# HIVE_SIGHT_DECAWAVE_A.net
KiCad netlist of a schematic drawn in Altium Designer
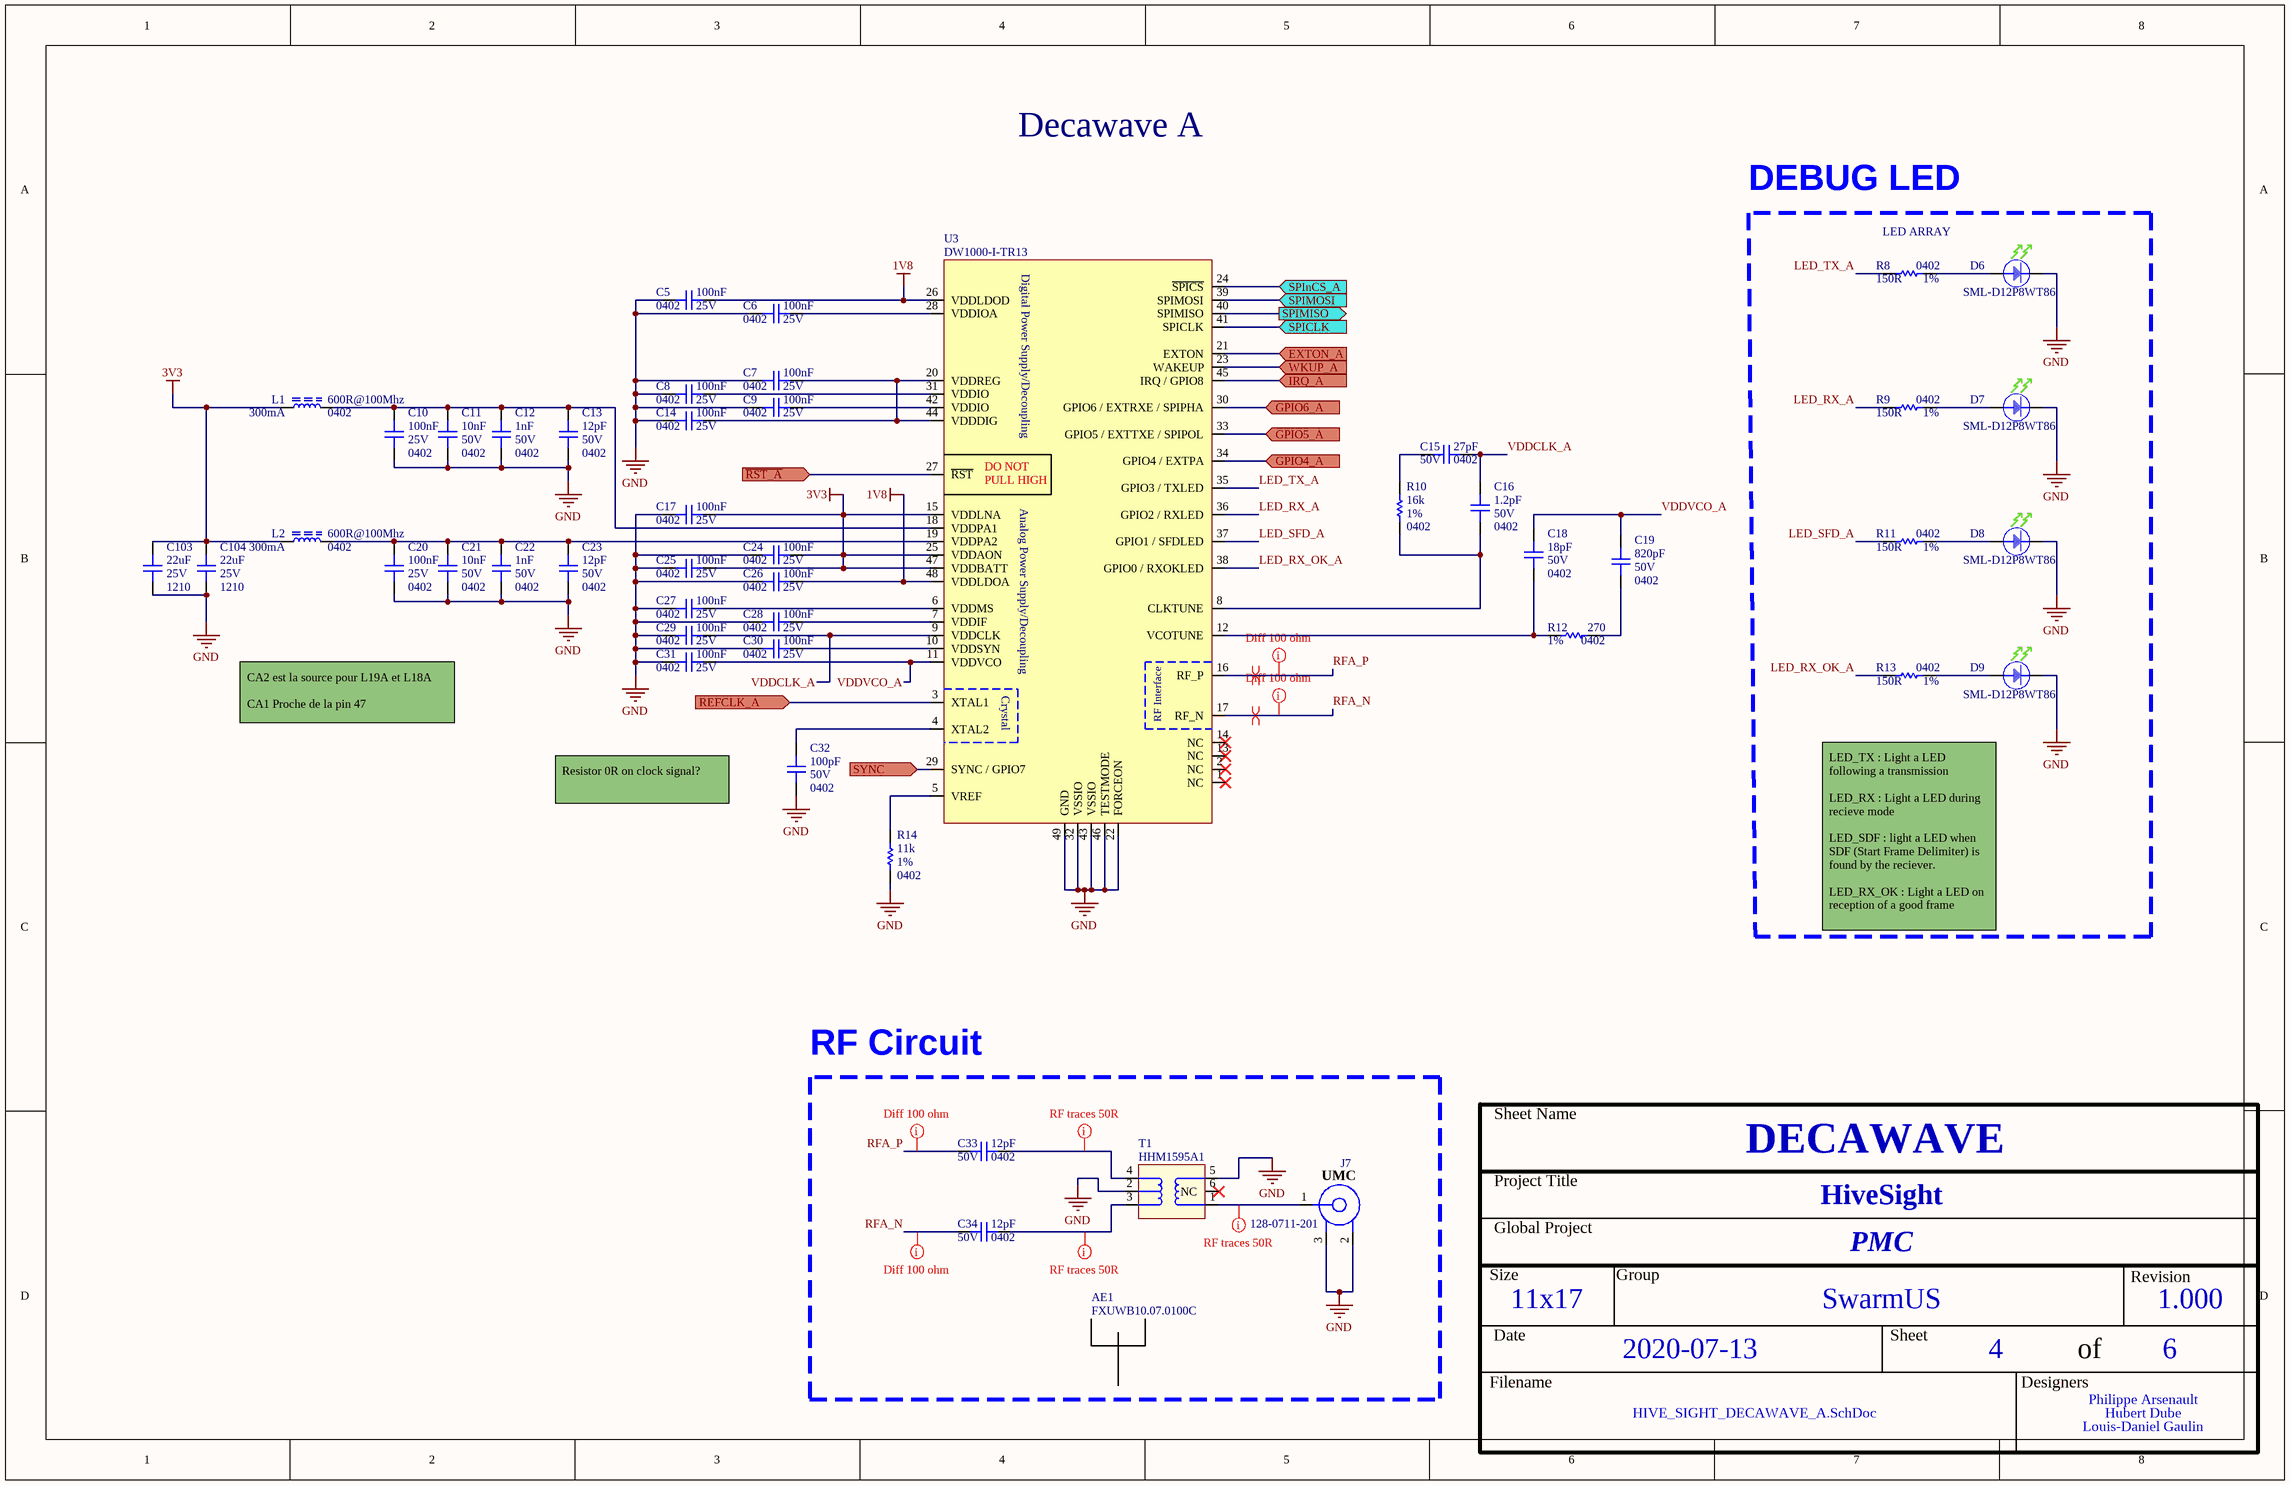
[diagram p0: HIVE_SIGHT_DECAWAVE_A.SchDoc]

(export (version "E")
  (design (tool "Eeschema 10.0.6"))
  (components
    (comp (ref "AE1")
      (value "FXUWB10.07.0100C")
      (description "External antenna - UWB - UMCC plug")
      (fields (field (name "CREATEDBY/DATE") "Philippe Arsenault"))
      (libsource (lib "SWARMUS_LIB") (part "ANT_FXUWB10.07.0100C"))
    )
    (comp (ref "C5")
      (value "100nF")
      (footprint "GRAMS_MASTER_LIB_PCB:CAP_CER_0402")
      (description "CAP - CER 0.1µF 10% 25V X7R - 0402")
      (fields
        (field (name "TOLERANCE") "10%")
        (field (name "PACKAGE") "0402")
        (field (name "VOLTAGE RATING") "25V")
        (field (name "Comment") "CGA2B3X7R1E104K050BB")
        (field (name "CREATEDBY/DATE") "Nicolas Roy 2018-11-07")
        (field (name "VERIFIEDBY") "Nicolas V. (2019-01-22)")
      )
      (libsource (lib "GRAMS_MASTER_LIB_SCH") (part "CAP_CER_CGA2B3X7R1E104K050BB"))
    )
    (comp (ref "C6")
      (value "100nF")
      (footprint "GRAMS_MASTER_LIB_PCB:CAP_CER_0402")
      (description "CAP - CER 0.1µF 10% 25V X7R - 0402")
      (fields
        (field (name "TOLERANCE") "10%")
        (field (name "PACKAGE") "0402")
        (field (name "VOLTAGE RATING") "25V")
        (field (name "Comment") "CGA2B3X7R1E104K050BB")
        (field (name "CREATEDBY/DATE") "Nicolas Roy 2018-11-07")
        (field (name "VERIFIEDBY") "Nicolas V. (2019-01-22)")
      )
      (libsource (lib "GRAMS_MASTER_LIB_SCH") (part "CAP_CER_CGA2B3X7R1E104K050BB"))
    )
    (comp (ref "C7")
      (value "100nF")
      (footprint "GRAMS_MASTER_LIB_PCB:CAP_CER_0402")
      (description "CAP - CER 0.1µF 10% 25V X7R - 0402")
      (fields
        (field (name "TOLERANCE") "10%")
        (field (name "PACKAGE") "0402")
        (field (name "VOLTAGE RATING") "25V")
        (field (name "Comment") "CGA2B3X7R1E104K050BB")
        (field (name "CREATEDBY/DATE") "Nicolas Roy 2018-11-07")
        (field (name "VERIFIEDBY") "Nicolas V. (2019-01-22)")
      )
      (libsource (lib "GRAMS_MASTER_LIB_SCH") (part "CAP_CER_CGA2B3X7R1E104K050BB"))
    )
    (comp (ref "C8")
      (value "100nF")
      (footprint "GRAMS_MASTER_LIB_PCB:CAP_CER_0402")
      (description "CAP - CER 0.1µF 10% 25V X7R - 0402")
      (fields
        (field (name "TOLERANCE") "10%")
        (field (name "PACKAGE") "0402")
        (field (name "VOLTAGE RATING") "25V")
        (field (name "Comment") "CGA2B3X7R1E104K050BB")
        (field (name "CREATEDBY/DATE") "Nicolas Roy 2018-11-07")
        (field (name "VERIFIEDBY") "Nicolas V. (2019-01-22)")
      )
      (libsource (lib "GRAMS_MASTER_LIB_SCH") (part "CAP_CER_CGA2B3X7R1E104K050BB"))
    )
    (comp (ref "C9")
      (value "100nF")
      (footprint "GRAMS_MASTER_LIB_PCB:CAP_CER_0402")
      (description "CAP - CER 0.1µF 10% 25V X7R - 0402")
      (fields
        (field (name "TOLERANCE") "10%")
        (field (name "PACKAGE") "0402")
        (field (name "VOLTAGE RATING") "25V")
        (field (name "Comment") "CGA2B3X7R1E104K050BB")
        (field (name "CREATEDBY/DATE") "Nicolas Roy 2018-11-07")
        (field (name "VERIFIEDBY") "Nicolas V. (2019-01-22)")
      )
      (libsource (lib "GRAMS_MASTER_LIB_SCH") (part "CAP_CER_CGA2B3X7R1E104K050BB"))
    )
    (comp (ref "C10")
      (value "100nF")
      (footprint "GRAMS_MASTER_LIB_PCB:CAP_CER_0402")
      (description "CAP - CER 0.1µF 10% 25V X7R - 0402")
      (fields
        (field (name "TOLERANCE") "10%")
        (field (name "PACKAGE") "0402")
        (field (name "VOLTAGE RATING") "25V")
        (field (name "Comment") "CGA2B3X7R1E104K050BB")
        (field (name "CREATEDBY/DATE") "Nicolas Roy 2018-11-07")
        (field (name "VERIFIEDBY") "Nicolas V. (2019-01-22)")
      )
      (libsource (lib "GRAMS_MASTER_LIB_SCH") (part "CAP_CER_CGA2B3X7R1E104K050BB"))
    )
    (comp (ref "C11")
      (value "10nF")
      (footprint "GRAMS_MASTER_LIB_PCB:CAP_CER_0402")
      (description "CAP - CER 10nF ±10% 50V X7R - 0402")
      (fields
        (field (name "TOLERANCE") "10%")
        (field (name "PACKAGE") "0402")
        (field (name "VOLTAGE RATING") "50V")
        (field (name "Comment") "CL05B103KB5NFNC")
        (field (name "CREATEDBY/DATE") "Keven Deslandes - 2018/11/20")
        (field (name "VERIFIEDBY") "Nicolas Roy - 2018/12/11")
      )
      (libsource (lib "GRAMS_MASTER_LIB_SCH") (part "CAP_CER_CL05B103KB5NFNC"))
    )
    (comp (ref "C12")
      (value "1nF")
      (footprint "CAP_CER_0402")
      (description "CAP - CER 1nF 10% 50V X7R - 0402")
      (fields
        (field (name "TOLERANCE") "10%")
        (field (name "PACKAGE") "0402")
        (field (name "VOLTAGE RATING") "50V")
        (field (name "Comment") "CC0402KRX7R9BB102")
        (field (name "CREATEDBY/DATE") "Jonathan Bouchard 2019-04-06")
        (field (name "VERIFIEDBY") "Nicolas V. (2019-04-30)")
      )
      (libsource (lib "GRAMS_MASTER_LIB_SCH") (part "CAP_CER_CC0402KRX7R9BB102"))
    )
    (comp (ref "C13")
      (value "12pF")
      (footprint "SWARMUS_LIB:CAP_CER_0402")
      (description "CAP - CER 12pF 50V ±5% C0G, NP0 - 0402")
      (fields
        (field (name "TOLERANCE") "±5%")
        (field (name "PACKAGE") "0402")
        (field (name "VOLTAGE RATING") "50V")
        (field (name "Comment") "CC0402JRNPO9BN120")
        (field (name "CREATEDBY/DATE") "Philippe Arsenault/ 2020-07-24")
        (field (name "VERIFIEDBY") "Louis-Daniel Gaulin / 2020-07-29")
      )
      (libsource (lib "SWARMUS_LIB") (part "CAP_CER_CC0402JRNPO9BN120"))
    )
    (comp (ref "C14")
      (value "100nF")
      (footprint "GRAMS_MASTER_LIB_PCB:CAP_CER_0402")
      (description "CAP - CER 0.1µF 10% 25V X7R - 0402")
      (fields
        (field (name "TOLERANCE") "10%")
        (field (name "PACKAGE") "0402")
        (field (name "VOLTAGE RATING") "25V")
        (field (name "Comment") "CGA2B3X7R1E104K050BB")
        (field (name "CREATEDBY/DATE") "Nicolas Roy 2018-11-07")
        (field (name "VERIFIEDBY") "Nicolas V. (2019-01-22)")
      )
      (libsource (lib "GRAMS_MASTER_LIB_SCH") (part "CAP_CER_CGA2B3X7R1E104K050BB"))
    )
    (comp (ref "C15")
      (value "27pF")
      (footprint "SWARMUS_LIB:CAP_CER_0402")
      (description "CAP - CER 27pF 50V ±5% C0G, NP0 - 0402")
      (fields
        (field (name "TOLERANCE") "±5%")
        (field (name "PACKAGE") "0402")
        (field (name "VOLTAGE RATING") "50V")
        (field (name "Comment") "CC0402JRNPO9BN270")
        (field (name "CREATEDBY/DATE") "Philippe Arsenault/ 2020-07-24")
        (field (name "VERIFIEDBY") "Louis-Daniel Gaulin / 2020-07-29")
      )
      (libsource (lib "SWARMUS_LIB") (part "CAP_CER_CC0402JRNPO9BN270"))
    )
    (comp (ref "C16")
      (value "1.2pF")
      (footprint "SWARMUS_LIB:CAP_CER_0402")
      (description "CAP - CER 1.2pF 50V ±0.25pF C0G, NP0 - 0402")
      (fields
        (field (name "TOLERANCE") "±0.25pF")
        (field (name "PACKAGE") "0402")
        (field (name "VOLTAGE RATING") "50V")
        (field (name "Comment") "C0402C129C5GACTU")
        (field (name "CREATEDBY/DATE") "Philippe Arsenault/ 2020-07-24")
        (field (name "VERIFIEDBY") "Louis-Daniel Gaulin / 2020-07-29")
      )
      (libsource (lib "SWARMUS_LIB") (part "CAP_CER_C0402C129C5GACTU"))
    )
    (comp (ref "C17")
      (value "100nF")
      (footprint "GRAMS_MASTER_LIB_PCB:CAP_CER_0402")
      (description "CAP - CER 0.1µF 10% 25V X7R - 0402")
      (fields
        (field (name "TOLERANCE") "10%")
        (field (name "PACKAGE") "0402")
        (field (name "VOLTAGE RATING") "25V")
        (field (name "Comment") "CGA2B3X7R1E104K050BB")
        (field (name "CREATEDBY/DATE") "Nicolas Roy 2018-11-07")
        (field (name "VERIFIEDBY") "Nicolas V. (2019-01-22)")
      )
      (libsource (lib "GRAMS_MASTER_LIB_SCH") (part "CAP_CER_CGA2B3X7R1E104K050BB"))
    )
    (comp (ref "C18")
      (value "18pF")
      (footprint "CAP_CER_0402")
      (description "CAP - CER 18pF 50V C0G, NPO - 0402")
      (fields
        (field (name "TOLERANCE") "2%")
        (field (name "PACKAGE") "0402")
        (field (name "VOLTAGE RATING") "50V")
        (field (name "Comment") "GRM1555C1H180GA01D")
        (field (name "CREATEDBY/DATE") "Tommy Rossignol / 2018-11-20")
        (field (name "VERIFIEDBY") "Caroline Paulin - 13 fév 2019")
      )
      (libsource (lib "GRAMS_MASTER_LIB_SCH") (part "CAP_CER_GRM1555C1H180GA01D"))
    )
    (comp (ref "C19")
      (value "820pF")
      (footprint "SWARMUS_LIB:CAP_CER_0402")
      (description "CAP - CER 820pF 50V ±10% X7R - 0402")
      (fields
        (field (name "TOLERANCE") "±10%")
        (field (name "PACKAGE") "0402")
        (field (name "VOLTAGE RATING") "50V")
        (field (name "Comment") "CC0402KRX7R9BB821")
        (field (name "CREATEDBY/DATE") "Philippe Arsenault/ 2020-07-24")
        (field (name "VERIFIEDBY") "Louis-Daniel Gaulin / 2020-07-29")
      )
      (libsource (lib "SWARMUS_LIB") (part "CAP_CER_CC0402KRX7R9BB821"))
    )
    (comp (ref "C20")
      (value "100nF")
      (footprint "GRAMS_MASTER_LIB_PCB:CAP_CER_0402")
      (description "CAP - CER 0.1µF 10% 25V X7R - 0402")
      (fields
        (field (name "TOLERANCE") "10%")
        (field (name "PACKAGE") "0402")
        (field (name "VOLTAGE RATING") "25V")
        (field (name "Comment") "CGA2B3X7R1E104K050BB")
        (field (name "CREATEDBY/DATE") "Nicolas Roy 2018-11-07")
        (field (name "VERIFIEDBY") "Nicolas V. (2019-01-22)")
      )
      (libsource (lib "GRAMS_MASTER_LIB_SCH") (part "CAP_CER_CGA2B3X7R1E104K050BB"))
    )
    (comp (ref "C21")
      (value "10nF")
      (footprint "GRAMS_MASTER_LIB_PCB:CAP_CER_0402")
      (description "CAP - CER 10nF ±10% 50V X7R - 0402")
      (fields
        (field (name "TOLERANCE") "10%")
        (field (name "PACKAGE") "0402")
        (field (name "VOLTAGE RATING") "50V")
        (field (name "Comment") "CL05B103KB5NFNC")
        (field (name "CREATEDBY/DATE") "Keven Deslandes - 2018/11/20")
        (field (name "VERIFIEDBY") "Nicolas Roy - 2018/12/11")
      )
      (libsource (lib "GRAMS_MASTER_LIB_SCH") (part "CAP_CER_CL05B103KB5NFNC"))
    )
    (comp (ref "C22")
      (value "1nF")
      (footprint "CAP_CER_0402")
      (description "CAP - CER 1nF 10% 50V X7R - 0402")
      (fields
        (field (name "TOLERANCE") "10%")
        (field (name "PACKAGE") "0402")
        (field (name "VOLTAGE RATING") "50V")
        (field (name "Comment") "CC0402KRX7R9BB102")
        (field (name "CREATEDBY/DATE") "Jonathan Bouchard 2019-04-06")
        (field (name "VERIFIEDBY") "Nicolas V. (2019-04-30)")
      )
      (libsource (lib "GRAMS_MASTER_LIB_SCH") (part "CAP_CER_CC0402KRX7R9BB102"))
    )
    (comp (ref "C23")
      (value "12pF")
      (footprint "SWARMUS_LIB:CAP_CER_0402")
      (description "CAP - CER 12pF 50V ±5% C0G, NP0 - 0402")
      (fields
        (field (name "TOLERANCE") "±5%")
        (field (name "PACKAGE") "0402")
        (field (name "VOLTAGE RATING") "50V")
        (field (name "Comment") "CC0402JRNPO9BN120")
        (field (name "CREATEDBY/DATE") "Philippe Arsenault/ 2020-07-24")
        (field (name "VERIFIEDBY") "Louis-Daniel Gaulin / 2020-07-29")
      )
      (libsource (lib "SWARMUS_LIB") (part "CAP_CER_CC0402JRNPO9BN120"))
    )
    (comp (ref "C24")
      (value "100nF")
      (footprint "GRAMS_MASTER_LIB_PCB:CAP_CER_0402")
      (description "CAP - CER 0.1µF 10% 25V X7R - 0402")
      (fields
        (field (name "TOLERANCE") "10%")
        (field (name "PACKAGE") "0402")
        (field (name "VOLTAGE RATING") "25V")
        (field (name "Comment") "CGA2B3X7R1E104K050BB")
        (field (name "CREATEDBY/DATE") "Nicolas Roy 2018-11-07")
        (field (name "VERIFIEDBY") "Nicolas V. (2019-01-22)")
      )
      (libsource (lib "GRAMS_MASTER_LIB_SCH") (part "CAP_CER_CGA2B3X7R1E104K050BB"))
    )
    (comp (ref "C25")
      (value "100nF")
      (footprint "GRAMS_MASTER_LIB_PCB:CAP_CER_0402")
      (description "CAP - CER 0.1µF 10% 25V X7R - 0402")
      (fields
        (field (name "TOLERANCE") "10%")
        (field (name "PACKAGE") "0402")
        (field (name "VOLTAGE RATING") "25V")
        (field (name "Comment") "CGA2B3X7R1E104K050BB")
        (field (name "CREATEDBY/DATE") "Nicolas Roy 2018-11-07")
        (field (name "VERIFIEDBY") "Nicolas V. (2019-01-22)")
      )
      (libsource (lib "GRAMS_MASTER_LIB_SCH") (part "CAP_CER_CGA2B3X7R1E104K050BB"))
    )
    (comp (ref "C26")
      (value "100nF")
      (footprint "GRAMS_MASTER_LIB_PCB:CAP_CER_0402")
      (description "CAP - CER 0.1µF 10% 25V X7R - 0402")
      (fields
        (field (name "TOLERANCE") "10%")
        (field (name "PACKAGE") "0402")
        (field (name "VOLTAGE RATING") "25V")
        (field (name "Comment") "CGA2B3X7R1E104K050BB")
        (field (name "CREATEDBY/DATE") "Nicolas Roy 2018-11-07")
        (field (name "VERIFIEDBY") "Nicolas V. (2019-01-22)")
      )
      (libsource (lib "GRAMS_MASTER_LIB_SCH") (part "CAP_CER_CGA2B3X7R1E104K050BB"))
    )
    (comp (ref "C27")
      (value "100nF")
      (footprint "GRAMS_MASTER_LIB_PCB:CAP_CER_0402")
      (description "CAP - CER 0.1µF 10% 25V X7R - 0402")
      (fields
        (field (name "TOLERANCE") "10%")
        (field (name "PACKAGE") "0402")
        (field (name "VOLTAGE RATING") "25V")
        (field (name "Comment") "CGA2B3X7R1E104K050BB")
        (field (name "CREATEDBY/DATE") "Nicolas Roy 2018-11-07")
        (field (name "VERIFIEDBY") "Nicolas V. (2019-01-22)")
      )
      (libsource (lib "GRAMS_MASTER_LIB_SCH") (part "CAP_CER_CGA2B3X7R1E104K050BB"))
    )
    (comp (ref "C28")
      (value "100nF")
      (footprint "GRAMS_MASTER_LIB_PCB:CAP_CER_0402")
      (description "CAP - CER 0.1µF 10% 25V X7R - 0402")
      (fields
        (field (name "TOLERANCE") "10%")
        (field (name "PACKAGE") "0402")
        (field (name "VOLTAGE RATING") "25V")
        (field (name "Comment") "CGA2B3X7R1E104K050BB")
        (field (name "CREATEDBY/DATE") "Nicolas Roy 2018-11-07")
        (field (name "VERIFIEDBY") "Nicolas V. (2019-01-22)")
      )
      (libsource (lib "GRAMS_MASTER_LIB_SCH") (part "CAP_CER_CGA2B3X7R1E104K050BB"))
    )
    (comp (ref "C29")
      (value "100nF")
      (footprint "GRAMS_MASTER_LIB_PCB:CAP_CER_0402")
      (description "CAP - CER 0.1µF 10% 25V X7R - 0402")
      (fields
        (field (name "TOLERANCE") "10%")
        (field (name "PACKAGE") "0402")
        (field (name "VOLTAGE RATING") "25V")
        (field (name "Comment") "CGA2B3X7R1E104K050BB")
        (field (name "CREATEDBY/DATE") "Nicolas Roy 2018-11-07")
        (field (name "VERIFIEDBY") "Nicolas V. (2019-01-22)")
      )
      (libsource (lib "GRAMS_MASTER_LIB_SCH") (part "CAP_CER_CGA2B3X7R1E104K050BB"))
    )
    (comp (ref "C30")
      (value "100nF")
      (footprint "GRAMS_MASTER_LIB_PCB:CAP_CER_0402")
      (description "CAP - CER 0.1µF 10% 25V X7R - 0402")
      (fields
        (field (name "TOLERANCE") "10%")
        (field (name "PACKAGE") "0402")
        (field (name "VOLTAGE RATING") "25V")
        (field (name "Comment") "CGA2B3X7R1E104K050BB")
        (field (name "CREATEDBY/DATE") "Nicolas Roy 2018-11-07")
        (field (name "VERIFIEDBY") "Nicolas V. (2019-01-22)")
      )
      (libsource (lib "GRAMS_MASTER_LIB_SCH") (part "CAP_CER_CGA2B3X7R1E104K050BB"))
    )
    (comp (ref "C31")
      (value "100nF")
      (footprint "GRAMS_MASTER_LIB_PCB:CAP_CER_0402")
      (description "CAP - CER 0.1µF 10% 25V X7R - 0402")
      (fields
        (field (name "TOLERANCE") "10%")
        (field (name "PACKAGE") "0402")
        (field (name "VOLTAGE RATING") "25V")
        (field (name "Comment") "CGA2B3X7R1E104K050BB")
        (field (name "CREATEDBY/DATE") "Nicolas Roy 2018-11-07")
        (field (name "VERIFIEDBY") "Nicolas V. (2019-01-22)")
      )
      (libsource (lib "GRAMS_MASTER_LIB_SCH") (part "CAP_CER_CGA2B3X7R1E104K050BB"))
    )
    (comp (ref "C32")
      (value "100pF")
      (footprint "SWARMUS_LIB:CAP_CER_0402")
      (description "CAP - CER 100pF 50V ±5% C0G,CP0 - 0402")
      (fields
        (field (name "TOLERANCE") "±5%")
        (field (name "PACKAGE") "0402")
        (field (name "VOLTAGE RATING") "50V")
        (field (name "Comment") "CC0402JRNPO9BN101")
        (field (name "CREATEDBY/DATE") "Philippe Arsenault/ 2020-07-24")
        (field (name "VERIFIEDBY") "Louis-Daniel Gaulin / 2020-07-29")
      )
      (libsource (lib "SWARMUS_LIB") (part "CAP_CER_CC0402JRNPO9BN101"))
    )
    (comp (ref "C33")
      (value "12pF")
      (footprint "SWARMUS_LIB:CAP_CER_0402")
      (description "CAP - CER 12pF 50V ±5% C0G, NP0 - 0402")
      (fields
        (field (name "TOLERANCE") "±5%")
        (field (name "PACKAGE") "0402")
        (field (name "VOLTAGE RATING") "50V")
        (field (name "Comment") "CC0402JRNPO9BN120")
        (field (name "CREATEDBY/DATE") "Philippe Arsenault/ 2020-07-24")
        (field (name "VERIFIEDBY") "Louis-Daniel Gaulin / 2020-07-29")
      )
      (libsource (lib "SWARMUS_LIB") (part "CAP_CER_CC0402JRNPO9BN120"))
    )
    (comp (ref "C34")
      (value "12pF")
      (footprint "SWARMUS_LIB:CAP_CER_0402")
      (description "CAP - CER 12pF 50V ±5% C0G, NP0 - 0402")
      (fields
        (field (name "TOLERANCE") "±5%")
        (field (name "PACKAGE") "0402")
        (field (name "VOLTAGE RATING") "50V")
        (field (name "Comment") "CC0402JRNPO9BN120")
        (field (name "CREATEDBY/DATE") "Philippe Arsenault/ 2020-07-24")
        (field (name "VERIFIEDBY") "Louis-Daniel Gaulin / 2020-07-29")
      )
      (libsource (lib "SWARMUS_LIB") (part "CAP_CER_CC0402JRNPO9BN120"))
    )
    (comp (ref "C103")
      (value "22uF")
      (footprint "GRAMS_MASTER_LIB_PCB:CAP_CER_1210")
      (description "CAP - CER 22UF 20% 25V X7R - 1210")
      (fields
        (field (name "TOLERANCE") "20%")
        (field (name "PACKAGE") "1210")
        (field (name "VOLTAGE RATING") "25V")
        (field (name "Comment") "C3225X7R1E226M250AB")
        (field (name "CREATEDBY/DATE") "Nicolas V. (2019-12-11)")
        (field (name "VERIFIEDBY") "Nicolas V. (2019-12-11)")
      )
      (libsource (lib "GRAMS_MASTER_LIB_SCH") (part "CAP_CER_C3225X7R1E226M250AB"))
    )
    (comp (ref "C104")
      (value "22uF")
      (footprint "GRAMS_MASTER_LIB_PCB:CAP_CER_1210")
      (description "CAP - CER 22UF 20% 25V X7R - 1210")
      (fields
        (field (name "TOLERANCE") "20%")
        (field (name "PACKAGE") "1210")
        (field (name "VOLTAGE RATING") "25V")
        (field (name "Comment") "C3225X7R1E226M250AB")
        (field (name "CREATEDBY/DATE") "Nicolas V. (2019-12-11)")
        (field (name "VERIFIEDBY") "Nicolas V. (2019-12-11)")
      )
      (libsource (lib "GRAMS_MASTER_LIB_SCH") (part "CAP_CER_C3225X7R1E226M250AB"))
    )
    (comp (ref "D6")
      (value "SML-D12P8WT86")
      (footprint "GRAMS_MASTER_LIB_PCB:LED_SML-D12P8WT86")
      (description "LED - GREEN DIFFUSED 0603 SMD - 0603")
      (fields
        (field (name "CREATEDBY/DATE") "Keven Deslandes - 2018/11/21")
        (field (name "VERIFIEDBY") "Caroline Paulin - 13 février 2019")
      )
      (libsource (lib "GRAMS_MASTER_LIB_SCH") (part "LED_SML-D12P8WT86"))
    )
    (comp (ref "D7")
      (value "SML-D12P8WT86")
      (footprint "GRAMS_MASTER_LIB_PCB:LED_SML-D12P8WT86")
      (description "LED - GREEN DIFFUSED 0603 SMD - 0603")
      (fields
        (field (name "CREATEDBY/DATE") "Keven Deslandes - 2018/11/21")
        (field (name "VERIFIEDBY") "Caroline Paulin - 13 février 2019")
      )
      (libsource (lib "GRAMS_MASTER_LIB_SCH") (part "LED_SML-D12P8WT86"))
    )
    (comp (ref "D8")
      (value "SML-D12P8WT86")
      (footprint "GRAMS_MASTER_LIB_PCB:LED_SML-D12P8WT86")
      (description "LED - GREEN DIFFUSED 0603 SMD - 0603")
      (fields
        (field (name "CREATEDBY/DATE") "Keven Deslandes - 2018/11/21")
        (field (name "VERIFIEDBY") "Caroline Paulin - 13 février 2019")
      )
      (libsource (lib "GRAMS_MASTER_LIB_SCH") (part "LED_SML-D12P8WT86"))
    )
    (comp (ref "D9")
      (value "SML-D12P8WT86")
      (footprint "GRAMS_MASTER_LIB_PCB:LED_SML-D12P8WT86")
      (description "LED - GREEN DIFFUSED 0603 SMD - 0603")
      (fields
        (field (name "CREATEDBY/DATE") "Keven Deslandes - 2018/11/21")
        (field (name "VERIFIEDBY") "Caroline Paulin - 13 février 2019")
      )
      (libsource (lib "GRAMS_MASTER_LIB_SCH") (part "LED_SML-D12P8WT86"))
    )
    (comp (ref "J7")
      (value "128-0711-201")
      (footprint "GRAMS_MASTER_LIB_PCB:CON_UMC_128-0711-201")
      (description "CON - UMC JACK STR 50 OHM - SMD")
      (fields
        (field (name "CREATEDBY/DATE") "Keven Desandes - 2018/09/27")
        (field (name "VERIFIEDBY") "Caroline Paulin - 23 janv 2019")
      )
      (libsource (lib "GRAMS_MASTER_LIB_SCH") (part "CON_UMC_128-0711-201"))
    )
    (comp (ref "L1")
      (value "600R@100Mhz")
      (footprint "GRAMS_MASTER_LIB_PCB:FER_0603")
      (description "FER - FERRITE BEAD 600 OHM@100MHz - 0402")
      (fields
        (field (name "CURRENT RATING") "300mA")
        (field (name "PACKAGE") "0402")
        (field (name "Comment") "BLM15AG601SN1D")
        (field (name "CREATEDBY/DATE") "Philippe Arsenault/2020-07-24")
      )
      (libsource (lib "a_Valider_PA") (part "FER_BLM15AG601SN1D"))
    )
    (comp (ref "L2")
      (value "600R@100Mhz")
      (footprint "GRAMS_MASTER_LIB_PCB:FER_0603")
      (description "FER - FERRITE BEAD 600 OHM@100MHz - 0402")
      (fields
        (field (name "CURRENT RATING") "300mA")
        (field (name "PACKAGE") "0402")
        (field (name "Comment") "BLM15AG601SN1D")
        (field (name "CREATEDBY/DATE") "Philippe Arsenault/2020-07-24")
      )
      (libsource (lib "a_Valider_PA") (part "FER_BLM15AG601SN1D"))
    )
    (comp (ref "R8")
      (value "150R")
      (footprint "RES_0402")
      (description "RES - 150R 1% 1/16W - 0402")
      (fields
        (field (name "TOLERANCE") "1%")
        (field (name "PACKAGE") "0402")
        (field (name "Comment") "RC0402FR-07150RL")
        (field (name "CREATEDBY/DATE") "Jonathan Bouchard 2019-03-25")
        (field (name "VERIFIEDBY") "Nicolas V. (2019-05-02)")
      )
      (libsource (lib "GRAMS_MASTER_LIB_SCH") (part "RES_RC0402FR-07150RL"))
    )
    (comp (ref "R9")
      (value "150R")
      (footprint "RES_0402")
      (description "RES - 150R 1% 1/16W - 0402")
      (fields
        (field (name "TOLERANCE") "1%")
        (field (name "PACKAGE") "0402")
        (field (name "Comment") "RC0402FR-07150RL")
        (field (name "CREATEDBY/DATE") "Jonathan Bouchard 2019-03-25")
        (field (name "VERIFIEDBY") "Nicolas V. (2019-05-02)")
      )
      (libsource (lib "GRAMS_MASTER_LIB_SCH") (part "RES_RC0402FR-07150RL"))
    )
    (comp (ref "R10")
      (value "16k")
      (footprint "GRAMS_MASTER_LIB_PCB:RES_0402")
      (description "RES - 16k OHM 1% 1/16W - 0402")
      (fields
        (field (name "TOLERANCE") "1%")
        (field (name "PACKAGE") "0402")
        (field (name "Comment") "RC0402FR-0716KL")
        (field (name "CREATEDBY/DATE") "Nicolas Roy/18 oct. 2018")
        (field (name "VERIFIEDBY") "Caroline Paulin - 18/12/2018")
      )
      (libsource (lib "GRAMS_MASTER_LIB_SCH") (part "RES_RC0402FR-0716KL"))
    )
    (comp (ref "R11")
      (value "150R")
      (footprint "RES_0402")
      (description "RES - 150R 1% 1/16W - 0402")
      (fields
        (field (name "TOLERANCE") "1%")
        (field (name "PACKAGE") "0402")
        (field (name "Comment") "RC0402FR-07150RL")
        (field (name "CREATEDBY/DATE") "Jonathan Bouchard 2019-03-25")
        (field (name "VERIFIEDBY") "Nicolas V. (2019-05-02)")
      )
      (libsource (lib "GRAMS_MASTER_LIB_SCH") (part "RES_RC0402FR-07150RL"))
    )
    (comp (ref "R12")
      (value "270")
      (footprint "FER_0402")
      (description "RES - 270R 1% 1/16W - 0402")
      (fields
        (field (name "TOLERANCE") "1%")
        (field (name "PACKAGE") "0402")
        (field (name "Comment") "RC0402FR-07270RL")
        (field (name "CREATEDBY/DATE") "Philippe Arsenault 2020-07-24")
        (field (name "VERIFIEDBY") "Louis-Daniel Gaulin / 03-10-2020")
      )
      (libsource (lib "SWARMUS_LIB") (part "RES_RC0402FR-07270RL"))
    )
    (comp (ref "R13")
      (value "150R")
      (footprint "RES_0402")
      (description "RES - 150R 1% 1/16W - 0402")
      (fields
        (field (name "TOLERANCE") "1%")
        (field (name "PACKAGE") "0402")
        (field (name "Comment") "RC0402FR-07150RL")
        (field (name "CREATEDBY/DATE") "Jonathan Bouchard 2019-03-25")
        (field (name "VERIFIEDBY") "Nicolas V. (2019-05-02)")
      )
      (libsource (lib "GRAMS_MASTER_LIB_SCH") (part "RES_RC0402FR-07150RL"))
    )
    (comp (ref "R14")
      (value "11k")
      (footprint "GRAMS_MASTER_LIB_PCB:RES_0402")
      (description "RES - 11K 1% 1/16W - 0402")
      (fields
        (field (name "TOLERANCE") "1%")
        (field (name "PACKAGE") "0402")
        (field (name "Comment") "RC0402FR-0711KL")
        (field (name "CREATEDBY/DATE") "Keven Deslandes 2018-10-15")
        (field (name "VERIFIEDBY") "Carolilne Paulin - 18/12/2018")
      )
      (libsource (lib "GRAMS_MASTER_LIB_SCH") (part "RES_RC0402FR-0711KL"))
    )
    (comp (ref "T1")
      (value "HHM1595A1")
      (footprint "XFR_HHM1595A1")
      (description "XFR - Imp Unbalaced/Balanced 50/100 3-8GHz  -SMD")
      (fields
        (field (name "CREATEDBY/DATE") "Philippe Arsenault/2020-21-07")
        (field (name "VERIFIEDBY") "Louis-Daniel Gaulin / 03-10-2020")
      )
      (libsource (lib "SWARMUS_LIB") (part "XFR_HHM1595A1"))
    )
    (comp (ref "U3")
      (value "DW1000-I-TR13")
      (footprint "SWARMUS_LIB:COM_XCV_DW1000-I-TR13")
      (description "COM - IC RF TxRx 802.15.4 IR-UWB DECAWAVE - 48-VFQFN EP")
      (fields (field (name "CREATEDBY/DATE") "Philippe Arsenault/13-07-2020"))
      (libsource (lib "SWARMUS_LIB") (part "COM_XCV_DW1000-I-TR13"))
    )
  )
  (nets
    (net (code "1") (name "/EXTON_A") (class "Default")
      (node (ref "U3") (pin "21") (pinfunction "EXTON_21") (pintype "passive"))
    )
    (net (code "2") (name "/GPIO4_A") (class "Default")
      (node (ref "U3") (pin "34") (pinfunction "GPIO4_/_EXTPA_34") (pintype "passive"))
    )
    (net (code "3") (name "/GPIO5_A") (class "Default")
      (node (ref "U3") (pin "33") (pinfunction "GPIO5_/_EXTTXE_/_SPIPOL_33") (pintype "passive"))
    )
    (net (code "4") (name "/GPIO6_A") (class "Default")
      (node (ref "U3") (pin "30") (pinfunction "GPIO6_/_EXTRXE_/_SPIPHA_30") (pintype "passive"))
    )
    (net (code "5") (name "/IRQ_A") (class "Default")
      (node (ref "U3") (pin "45") (pinfunction "IRQ_/_GPIO8_45") (pintype "passive"))
    )
    (net (code "6") (name "/LED_RX_A") (class "Default")
      (node (ref "R9") (pin "2") (pinfunction "2_2") (pintype "passive"))
      (node (ref "U3") (pin "36") (pinfunction "GPIO2_/_RXLED_36") (pintype "passive"))
    )
    (net (code "7") (name "/LED_RX_OK_A") (class "Default")
      (node (ref "R13") (pin "2") (pinfunction "2_2") (pintype "passive"))
      (node (ref "U3") (pin "38") (pinfunction "GPIO0_/_RXOKLED_38") (pintype "passive"))
    )
    (net (code "8") (name "/LED_SFD_A") (class "Default")
      (node (ref "R11") (pin "2") (pinfunction "2_2") (pintype "passive"))
      (node (ref "U3") (pin "37") (pinfunction "GPIO1_/_SFDLED_37") (pintype "passive"))
    )
    (net (code "9") (name "/LED_TX_A") (class "Default")
      (node (ref "R8") (pin "2") (pinfunction "2_2") (pintype "passive"))
      (node (ref "U3") (pin "35") (pinfunction "GPIO3_/_TXLED_35") (pintype "passive"))
    )
    (net (code "10") (name "/REFCLK_A") (class "Default")
      (node (ref "U3") (pin "3") (pinfunction "XTAL1_3") (pintype "passive"))
    )
    (net (code "11") (name "/RFA_N") (class "Default")
      (node (ref "C34") (pin "2") (pinfunction "2_2") (pintype "passive"))
      (node (ref "U3") (pin "17") (pinfunction "RF_N_17") (pintype "passive"))
    )
    (net (code "12") (name "/RFA_P") (class "Default")
      (node (ref "C33") (pin "2") (pinfunction "2_2") (pintype "passive"))
      (node (ref "U3") (pin "16") (pinfunction "RF_P_16") (pintype "passive"))
    )
    (net (code "13") (name "/RST_A") (class "Default")
      (node (ref "U3") (pin "27") (pinfunction "RST_27") (pintype "passive"))
    )
    (net (code "14") (name "/SPICLK") (class "Default")
      (node (ref "U3") (pin "41") (pinfunction "SPICLK_41") (pintype "passive"))
    )
    (net (code "15") (name "/SPIMISO") (class "Default")
      (node (ref "U3") (pin "40") (pinfunction "SPIMISO_40") (pintype "passive"))
    )
    (net (code "16") (name "/SPIMOSI") (class "Default")
      (node (ref "U3") (pin "39") (pinfunction "SPIMOSI_39") (pintype "passive"))
    )
    (net (code "17") (name "/SPInCS_A") (class "Default")
      (node (ref "U3") (pin "24") (pinfunction "SPICS_24") (pintype "passive"))
    )
    (net (code "18") (name "/SYNC") (class "Default")
      (node (ref "U3") (pin "29") (pinfunction "SYNC_/_GPIO7_29") (pintype "passive"))
    )
    (net (code "19") (name "/VDDCLK_A") (class "Default")
      (node (ref "C15") (pin "1") (pinfunction "1_1") (pintype "passive"))
      (node (ref "C16") (pin "2") (pinfunction "2_2") (pintype "passive"))
      (node (ref "C29") (pin "1") (pinfunction "1_1") (pintype "passive"))
      (node (ref "U3") (pin "9") (pinfunction "VDDCLK_9") (pintype "passive"))
    )
    (net (code "20") (name "/VDDVCO_A") (class "Default")
      (node (ref "C18") (pin "2") (pinfunction "2_2") (pintype "passive"))
      (node (ref "C19") (pin "2") (pinfunction "2_2") (pintype "passive"))
      (node (ref "C31") (pin "1") (pinfunction "1_1") (pintype "passive"))
      (node (ref "U3") (pin "11") (pinfunction "VDDVCO_11") (pintype "passive"))
    )
    (net (code "21") (name "/WKUP_A") (class "Default")
      (node (ref "U3") (pin "23") (pinfunction "WAKEUP_23") (pintype "passive"))
    )
    (net (code "22") (name "1V8") (class "Default")
      (node (ref "C26") (pin "1") (pinfunction "1_1") (pintype "passive"))
      (node (ref "C5") (pin "1") (pinfunction "1_1") (pintype "passive"))
      (node (ref "U3") (pin "26") (pinfunction "VDDLDOD_26") (pintype "passive"))
      (node (ref "U3") (pin "48") (pinfunction "VDDLDOA_48") (pintype "passive"))
    )
    (net (code "23") (name "3V3") (class "Default")
      (node (ref "C103") (pin "2") (pinfunction "2_2") (pintype "passive"))
      (node (ref "C104") (pin "2") (pinfunction "2_2") (pintype "passive"))
      (node (ref "C17") (pin "1") (pinfunction "1_1") (pintype "passive"))
      (node (ref "C24") (pin "1") (pinfunction "1_1") (pintype "passive"))
      (node (ref "C25") (pin "1") (pinfunction "1_1") (pintype "passive"))
      (node (ref "L1") (pin "1") (pinfunction "1_1") (pintype "passive"))
      (node (ref "L2") (pin "1") (pinfunction "1_1") (pintype "passive"))
      (node (ref "U3") (pin "15") (pinfunction "VDDLNA_15") (pintype "passive"))
      (node (ref "U3") (pin "25") (pinfunction "VDDAON_25") (pintype "passive"))
      (node (ref "U3") (pin "47") (pinfunction "VDDBATT_47") (pintype "passive"))
    )
    (net (code "24") (name "GND") (class "Default")
      (node (ref "C10") (pin "1") (pinfunction "1_1") (pintype "passive"))
      (node (ref "C103") (pin "1") (pinfunction "1_1") (pintype "passive"))
      (node (ref "C104") (pin "1") (pinfunction "1_1") (pintype "passive"))
      (node (ref "C11") (pin "1") (pinfunction "1_1") (pintype "passive"))
      (node (ref "C12") (pin "1") (pinfunction "1_1") (pintype "passive"))
      (node (ref "C13") (pin "1") (pinfunction "1_1") (pintype "passive"))
      (node (ref "C14") (pin "2") (pinfunction "2_2") (pintype "passive"))
      (node (ref "C17") (pin "2") (pinfunction "2_2") (pintype "passive"))
      (node (ref "C20") (pin "1") (pinfunction "1_1") (pintype "passive"))
      (node (ref "C21") (pin "1") (pinfunction "1_1") (pintype "passive"))
      (node (ref "C22") (pin "1") (pinfunction "1_1") (pintype "passive"))
      (node (ref "C23") (pin "1") (pinfunction "1_1") (pintype "passive"))
      (node (ref "C24") (pin "2") (pinfunction "2_2") (pintype "passive"))
      (node (ref "C25") (pin "2") (pinfunction "2_2") (pintype "passive"))
      (node (ref "C26") (pin "2") (pinfunction "2_2") (pintype "passive"))
      (node (ref "C27") (pin "2") (pinfunction "2_2") (pintype "passive"))
      (node (ref "C28") (pin "2") (pinfunction "2_2") (pintype "passive"))
      (node (ref "C29") (pin "2") (pinfunction "2_2") (pintype "passive"))
      (node (ref "C30") (pin "2") (pinfunction "2_2") (pintype "passive"))
      (node (ref "C31") (pin "2") (pinfunction "2_2") (pintype "passive"))
      (node (ref "C32") (pin "1") (pinfunction "1_1") (pintype "passive"))
      (node (ref "C5") (pin "2") (pinfunction "2_2") (pintype "passive"))
      (node (ref "C6") (pin "2") (pinfunction "2_2") (pintype "passive"))
      (node (ref "C7") (pin "2") (pinfunction "2_2") (pintype "passive"))
      (node (ref "C8") (pin "2") (pinfunction "2_2") (pintype "passive"))
      (node (ref "C9") (pin "2") (pinfunction "2_2") (pintype "passive"))
      (node (ref "D6") (pin "K") (pinfunction "K_K") (pintype "passive"))
      (node (ref "D7") (pin "K") (pinfunction "K_K") (pintype "passive"))
      (node (ref "D8") (pin "K") (pinfunction "K_K") (pintype "passive"))
      (node (ref "D9") (pin "K") (pinfunction "K_K") (pintype "passive"))
      (node (ref "J7") (pin "2") (pinfunction "2_2") (pintype "passive"))
      (node (ref "J7") (pin "3") (pinfunction "3_3") (pintype "passive"))
      (node (ref "R14") (pin "1") (pinfunction "1_1") (pintype "passive"))
      (node (ref "T1") (pin "2") (pinfunction "GND_2") (pintype "passive"))
      (node (ref "T1") (pin "5") (pinfunction "5_5") (pintype "passive"))
      (node (ref "U3") (pin "22") (pinfunction "FORCEON_22") (pintype "passive"))
      (node (ref "U3") (pin "32") (pinfunction "VSSIO_32") (pintype "passive"))
      (node (ref "U3") (pin "43") (pinfunction "VSSIO_43") (pintype "passive"))
      (node (ref "U3") (pin "46") (pinfunction "TESTMODE_46") (pintype "passive"))
      (node (ref "U3") (pin "49") (pinfunction "GND_49") (pintype "passive"))
    )
    (net (code "25") (name "Net-(C8-Pad1)") (class "Default")
      (node (ref "C8") (pin "1") (pinfunction "1_1") (pintype "passive"))
      (node (ref "U3") (pin "31") (pinfunction "VDDIO_31") (pintype "passive"))
    )
    (net (code "26") (name "Net-(C9-Pad1)") (class "Default")
      (node (ref "C9") (pin "1") (pinfunction "1_1") (pintype "passive"))
      (node (ref "U3") (pin "42") (pinfunction "VDDIO_42") (pintype "passive"))
    )
    (net (code "27") (name "Net-(C15-Pad2)") (class "Default")
      (node (ref "C15") (pin "2") (pinfunction "2_2") (pintype "passive"))
      (node (ref "R10") (pin "2") (pinfunction "2_2") (pintype "passive"))
    )
    (net (code "28") (name "Net-(C19-Pad1)") (class "Default")
      (node (ref "C19") (pin "1") (pinfunction "1_1") (pintype "passive"))
      (node (ref "R12") (pin "1") (pinfunction "1_1") (pintype "passive"))
    )
    (net (code "29") (name "Net-(C33-Pad1)") (class "Default")
      (node (ref "C33") (pin "1") (pinfunction "1_1") (pintype "passive"))
      (node (ref "T1") (pin "4") (pinfunction "4_4") (pintype "passive"))
    )
    (net (code "30") (name "Net-(C34-Pad1)") (class "Default")
      (node (ref "C34") (pin "1") (pinfunction "1_1") (pintype "passive"))
      (node (ref "T1") (pin "3") (pinfunction "3_3") (pintype "passive"))
    )
    (net (code "31") (name "Net-(D6-PadA)") (class "Default")
      (node (ref "D6") (pin "A") (pinfunction "A_A") (pintype "passive"))
      (node (ref "R8") (pin "1") (pinfunction "1_1") (pintype "passive"))
    )
    (net (code "32") (name "Net-(D7-PadA)") (class "Default")
      (node (ref "D7") (pin "A") (pinfunction "A_A") (pintype "passive"))
      (node (ref "R9") (pin "1") (pinfunction "1_1") (pintype "passive"))
    )
    (net (code "33") (name "Net-(D8-PadA)") (class "Default")
      (node (ref "D8") (pin "A") (pinfunction "A_A") (pintype "passive"))
      (node (ref "R11") (pin "1") (pinfunction "1_1") (pintype "passive"))
    )
    (net (code "34") (name "Net-(D9-PadA)") (class "Default")
      (node (ref "D9") (pin "A") (pinfunction "A_A") (pintype "passive"))
      (node (ref "R13") (pin "1") (pinfunction "1_1") (pintype "passive"))
    )
    (net (code "35") (name "Net-(J7-Pad1)") (class "Default")
      (node (ref "J7") (pin "1") (pinfunction "1_1") (pintype "passive"))
      (node (ref "T1") (pin "1") (pinfunction "1_1") (pintype "passive"))
    )
    (net (code "36") (name "Net-(U3-CLKTUNE)") (class "Default")
      (node (ref "C16") (pin "1") (pinfunction "1_1") (pintype "passive"))
      (node (ref "R10") (pin "1") (pinfunction "1_1") (pintype "passive"))
      (node (ref "U3") (pin "8") (pinfunction "CLKTUNE_8") (pintype "passive"))
    )
    (net (code "37") (name "Net-(U3-VCOTUNE)") (class "Default")
      (node (ref "C18") (pin "1") (pinfunction "1_1") (pintype "passive"))
      (node (ref "R12") (pin "2") (pinfunction "2_2") (pintype "passive"))
      (node (ref "U3") (pin "12") (pinfunction "VCOTUNE_12") (pintype "passive"))
    )
    (net (code "38") (name "Net-(U3-VDDDIG)") (class "Default")
      (node (ref "C14") (pin "1") (pinfunction "1_1") (pintype "passive"))
      (node (ref "C7") (pin "1") (pinfunction "1_1") (pintype "passive"))
      (node (ref "U3") (pin "20") (pinfunction "VDDREG_20") (pintype "passive"))
      (node (ref "U3") (pin "44") (pinfunction "VDDDIG_44") (pintype "passive"))
    )
    (net (code "39") (name "Net-(U3-VDDIF)") (class "Default")
      (node (ref "C28") (pin "1") (pinfunction "1_1") (pintype "passive"))
      (node (ref "U3") (pin "7") (pinfunction "VDDIF_7") (pintype "passive"))
    )
    (net (code "40") (name "Net-(U3-VDDIOA)") (class "Default")
      (node (ref "C6") (pin "1") (pinfunction "1_1") (pintype "passive"))
      (node (ref "U3") (pin "28") (pinfunction "VDDIOA_28") (pintype "passive"))
    )
    (net (code "41") (name "Net-(U3-VDDMS)") (class "Default")
      (node (ref "C27") (pin "1") (pinfunction "1_1") (pintype "passive"))
      (node (ref "U3") (pin "6") (pinfunction "VDDMS_6") (pintype "passive"))
    )
    (net (code "42") (name "Net-(U3-VDDPA1)") (class "Default")
      (node (ref "C10") (pin "2") (pinfunction "2_2") (pintype "passive"))
      (node (ref "C11") (pin "2") (pinfunction "2_2") (pintype "passive"))
      (node (ref "C12") (pin "2") (pinfunction "2_2") (pintype "passive"))
      (node (ref "C13") (pin "2") (pinfunction "2_2") (pintype "passive"))
      (node (ref "L1") (pin "2") (pinfunction "2_2") (pintype "passive"))
      (node (ref "U3") (pin "18") (pinfunction "VDDPA1_18") (pintype "passive"))
    )
    (net (code "43") (name "Net-(U3-VDDPA2)") (class "Default")
      (node (ref "C20") (pin "2") (pinfunction "2_2") (pintype "passive"))
      (node (ref "C21") (pin "2") (pinfunction "2_2") (pintype "passive"))
      (node (ref "C22") (pin "2") (pinfunction "2_2") (pintype "passive"))
      (node (ref "C23") (pin "2") (pinfunction "2_2") (pintype "passive"))
      (node (ref "L2") (pin "2") (pinfunction "2_2") (pintype "passive"))
      (node (ref "U3") (pin "19") (pinfunction "VDDPA2_19") (pintype "passive"))
    )
    (net (code "44") (name "Net-(U3-VDDSYN)") (class "Default")
      (node (ref "C30") (pin "1") (pinfunction "1_1") (pintype "passive"))
      (node (ref "U3") (pin "10") (pinfunction "VDDSYN_10") (pintype "passive"))
    )
    (net (code "45") (name "Net-(U3-VREF)") (class "Default")
      (node (ref "R14") (pin "2") (pinfunction "2_2") (pintype "passive"))
      (node (ref "U3") (pin "5") (pinfunction "VREF_5") (pintype "passive"))
    )
    (net (code "46") (name "Net-(U3-XTAL2)") (class "Default")
      (node (ref "C32") (pin "2") (pinfunction "2_2") (pintype "passive"))
      (node (ref "U3") (pin "4") (pinfunction "XTAL2_4") (pintype "passive"))
    )
    (net (code "47") (name "unconnected-(T1-NC-Pad6)") (class "Default")
      (node (ref "T1") (pin "6") (pinfunction "NC_6") (pintype "passive+no_connect"))
    )
    (net (code "48") (name "unconnected-(U3-NC-Pad1)") (class "Default")
      (node (ref "U3") (pin "1") (pinfunction "NC_1") (pintype "passive+no_connect"))
    )
    (net (code "49") (name "unconnected-(U3-NC-Pad2)") (class "Default")
      (node (ref "U3") (pin "2") (pinfunction "NC_2") (pintype "passive+no_connect"))
    )
    (net (code "50") (name "unconnected-(U3-NC-Pad13)") (class "Default")
      (node (ref "U3") (pin "13") (pinfunction "NC_13") (pintype "passive+no_connect"))
    )
    (net (code "51") (name "unconnected-(U3-NC-Pad14)") (class "Default")
      (node (ref "U3") (pin "14") (pinfunction "NC_14") (pintype "passive+no_connect"))
    )
  )
)
